# PIC16F15376-breakout.net
KiCad netlist of a schematic drawn in EAGLE
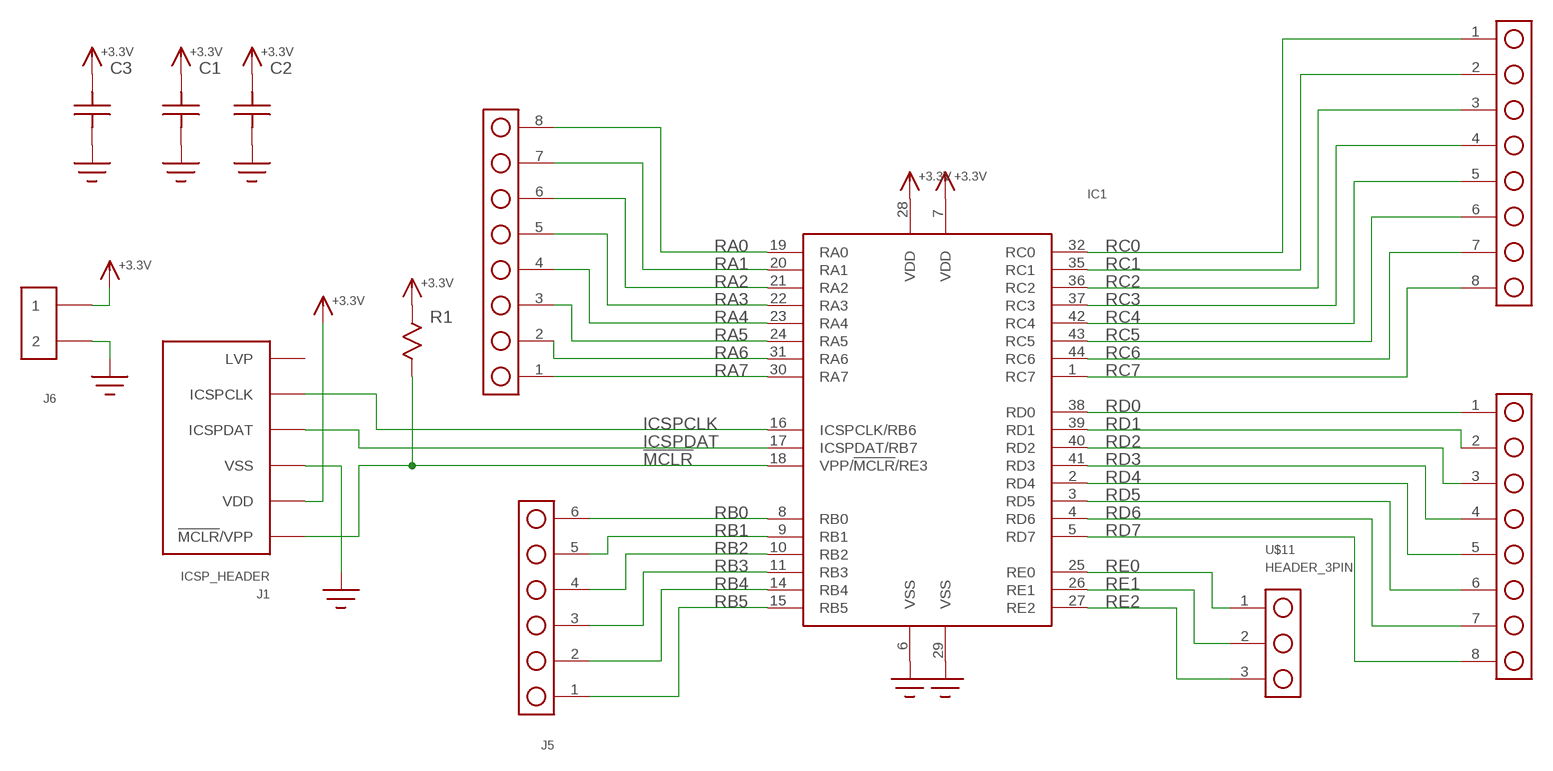
[diagram p0: schematic, sheet 1]

(export (version "E")
  (design (tool "Eeschema 10.0.6"))
  (components
    (comp (ref "C1")
      (value "C0603")
      (footprint "eagle-import:C0603")
      (libsource (lib "eagle-import") (part "C0603"))
    )
    (comp (ref "C2")
      (value "C0603")
      (footprint "eagle-import:C0603")
      (libsource (lib "eagle-import") (part "C0603"))
    )
    (comp (ref "C3")
      (value "C1206")
      (footprint "eagle-import:1206")
      (libsource (lib "eagle-import") (part "C1206"))
    )
    (comp (ref "IC1")
      (value "PIC16F15376")
      (footprint "eagle-import:TQFP44")
      (libsource (lib "eagle-import") (part "PIC16F15376"))
    )
    (comp (ref "J1")
      (value "ICSP_HEADER")
      (footprint "eagle-import:HEADER_6PIN")
      (libsource (lib "eagle-import") (part "ICSP_HEADER"))
    )
    (comp (ref "J2")
      (value "HEADER_8PIN")
      (footprint "eagle-import:HEADER_8_PIN")
      (libsource (lib "eagle-import") (part "HEADER_8PIN"))
    )
    (comp (ref "J3")
      (value "HEADER_8PIN")
      (footprint "eagle-import:HEADER_8_PIN")
      (libsource (lib "eagle-import") (part "HEADER_8PIN"))
    )
    (comp (ref "J4")
      (value "HEADER_8PIN")
      (footprint "eagle-import:HEADER_8_PIN")
      (libsource (lib "eagle-import") (part "HEADER_8PIN"))
    )
    (comp (ref "J5")
      (value "HEADER_6PIN")
      (footprint "eagle-import:HEADER_6PIN")
      (libsource (lib "eagle-import") (part "HEADER_6PIN"))
    )
    (comp (ref "J6")
      (value "HEADER_2PIN")
      (footprint "eagle-import:HEADER_2PIN")
      (libsource (lib "eagle-import") (part "HEADER_2PIN"))
    )
    (comp (ref "R1")
      (value "R0603")
      (footprint "eagle-import:R0603")
      (libsource (lib "eagle-import") (part "R0603"))
    )
    (comp (ref "U$11")
      (value "HEADER_3PIN")
      (footprint "eagle-import:HEADER_3PIN")
      (libsource (lib "eagle-import") (part "HEADER_3PIN"))
    )
  )
  (nets
    (net (code "1") (name "+3.3V") (class "Default")
      (node (ref "C1") (pin "P$2") (pinfunction "P$2_P$2") (pintype "bidirectional"))
      (node (ref "C2") (pin "P$2") (pinfunction "P$2_P$2") (pintype "bidirectional"))
      (node (ref "C3") (pin "P$2") (pinfunction "P$2_P$2") (pintype "bidirectional"))
      (node (ref "IC1") (pin "28") (pinfunction "VDD_28") (pintype "bidirectional"))
      (node (ref "IC1") (pin "7") (pinfunction "VDD_7") (pintype "bidirectional"))
      (node (ref "J1") (pin "2") (pinfunction "VDD_2") (pintype "bidirectional"))
      (node (ref "J6") (pin "1") (pinfunction "1_1") (pintype "bidirectional"))
      (node (ref "R1") (pin "P$1") (pinfunction "P$3_P$1") (pintype "bidirectional"))
    )
    (net (code "2") (name "/ICSPCLK") (class "Default")
      (node (ref "IC1") (pin "16") (pinfunction "ICSPCLK/RB6_16") (pintype "bidirectional"))
      (node (ref "J1") (pin "5") (pinfunction "ICSPCLK_5") (pintype "bidirectional"))
    )
    (net (code "3") (name "/ICSPDAT") (class "Default")
      (node (ref "IC1") (pin "17") (pinfunction "ICSPDAT/RB7_17") (pintype "bidirectional"))
      (node (ref "J1") (pin "4") (pinfunction "ICSPDAT_4") (pintype "bidirectional"))
    )
    (net (code "4") (name "/RA0") (class "Default")
      (node (ref "IC1") (pin "19") (pinfunction "RA0_19") (pintype "bidirectional"))
      (node (ref "J2") (pin "8") (pinfunction "8_8") (pintype "bidirectional"))
    )
    (net (code "5") (name "/RA1") (class "Default")
      (node (ref "IC1") (pin "20") (pinfunction "RA1_20") (pintype "bidirectional"))
      (node (ref "J2") (pin "7") (pinfunction "7_7") (pintype "bidirectional"))
    )
    (net (code "6") (name "/RA2") (class "Default")
      (node (ref "IC1") (pin "21") (pinfunction "RA2_21") (pintype "bidirectional"))
      (node (ref "J2") (pin "6") (pinfunction "6_6") (pintype "bidirectional"))
    )
    (net (code "7") (name "/RA3") (class "Default")
      (node (ref "IC1") (pin "22") (pinfunction "RA3_22") (pintype "bidirectional"))
      (node (ref "J2") (pin "5") (pinfunction "5_5") (pintype "bidirectional"))
    )
    (net (code "8") (name "/RA4") (class "Default")
      (node (ref "IC1") (pin "23") (pinfunction "RA4_23") (pintype "bidirectional"))
      (node (ref "J2") (pin "4") (pinfunction "4_4") (pintype "bidirectional"))
    )
    (net (code "9") (name "/RA5") (class "Default")
      (node (ref "IC1") (pin "24") (pinfunction "RA5_24") (pintype "bidirectional"))
      (node (ref "J2") (pin "3") (pinfunction "3_3") (pintype "bidirectional"))
    )
    (net (code "10") (name "/RA6") (class "Default")
      (node (ref "IC1") (pin "31") (pinfunction "RA6_31") (pintype "bidirectional"))
      (node (ref "J2") (pin "2") (pinfunction "2_2") (pintype "bidirectional"))
    )
    (net (code "11") (name "/RA7") (class "Default")
      (node (ref "IC1") (pin "30") (pinfunction "RA7_30") (pintype "bidirectional"))
      (node (ref "J2") (pin "1") (pinfunction "1_1") (pintype "bidirectional"))
    )
    (net (code "12") (name "/RB0") (class "Default")
      (node (ref "IC1") (pin "8") (pinfunction "RB0_8") (pintype "bidirectional"))
      (node (ref "J5") (pin "6") (pinfunction "6_6") (pintype "bidirectional"))
    )
    (net (code "13") (name "/RB1") (class "Default")
      (node (ref "IC1") (pin "9") (pinfunction "RB1_9") (pintype "bidirectional"))
      (node (ref "J5") (pin "5") (pinfunction "5_5") (pintype "bidirectional"))
    )
    (net (code "14") (name "/RB2") (class "Default")
      (node (ref "IC1") (pin "10") (pinfunction "RB2_10") (pintype "bidirectional"))
      (node (ref "J5") (pin "4") (pinfunction "4_4") (pintype "bidirectional"))
    )
    (net (code "15") (name "/RB3") (class "Default")
      (node (ref "IC1") (pin "11") (pinfunction "RB3_11") (pintype "bidirectional"))
      (node (ref "J5") (pin "3") (pinfunction "3_3") (pintype "bidirectional"))
    )
    (net (code "16") (name "/RB4") (class "Default")
      (node (ref "IC1") (pin "14") (pinfunction "RB4_14") (pintype "bidirectional"))
      (node (ref "J5") (pin "2") (pinfunction "2_2") (pintype "bidirectional"))
    )
    (net (code "17") (name "/RB5") (class "Default")
      (node (ref "IC1") (pin "15") (pinfunction "RB5_15") (pintype "bidirectional"))
      (node (ref "J5") (pin "1") (pinfunction "1_1") (pintype "bidirectional"))
    )
    (net (code "18") (name "/RC0") (class "Default")
      (node (ref "IC1") (pin "32") (pinfunction "RC0_32") (pintype "bidirectional"))
      (node (ref "J3") (pin "1") (pinfunction "1_1") (pintype "bidirectional"))
    )
    (net (code "19") (name "/RC1") (class "Default")
      (node (ref "IC1") (pin "35") (pinfunction "RC1_35") (pintype "bidirectional"))
      (node (ref "J3") (pin "2") (pinfunction "2_2") (pintype "bidirectional"))
    )
    (net (code "20") (name "/RC2") (class "Default")
      (node (ref "IC1") (pin "36") (pinfunction "RC2_36") (pintype "bidirectional"))
      (node (ref "J3") (pin "3") (pinfunction "3_3") (pintype "bidirectional"))
    )
    (net (code "21") (name "/RC3") (class "Default")
      (node (ref "IC1") (pin "37") (pinfunction "RC3_37") (pintype "bidirectional"))
      (node (ref "J3") (pin "4") (pinfunction "4_4") (pintype "bidirectional"))
    )
    (net (code "22") (name "/RC4") (class "Default")
      (node (ref "IC1") (pin "42") (pinfunction "RC4_42") (pintype "bidirectional"))
      (node (ref "J3") (pin "5") (pinfunction "5_5") (pintype "bidirectional"))
    )
    (net (code "23") (name "/RC5") (class "Default")
      (node (ref "IC1") (pin "43") (pinfunction "RC5_43") (pintype "bidirectional"))
      (node (ref "J3") (pin "6") (pinfunction "6_6") (pintype "bidirectional"))
    )
    (net (code "24") (name "/RC6") (class "Default")
      (node (ref "IC1") (pin "44") (pinfunction "RC6_44") (pintype "bidirectional"))
      (node (ref "J3") (pin "7") (pinfunction "7_7") (pintype "bidirectional"))
    )
    (net (code "25") (name "/RC7") (class "Default")
      (node (ref "IC1") (pin "1") (pinfunction "RC7_1") (pintype "bidirectional"))
      (node (ref "J3") (pin "8") (pinfunction "8_8") (pintype "bidirectional"))
    )
    (net (code "26") (name "/RD0") (class "Default")
      (node (ref "IC1") (pin "38") (pinfunction "RD0_38") (pintype "bidirectional"))
      (node (ref "J4") (pin "1") (pinfunction "1_1") (pintype "bidirectional"))
    )
    (net (code "27") (name "/RD1") (class "Default")
      (node (ref "IC1") (pin "39") (pinfunction "RD1_39") (pintype "bidirectional"))
      (node (ref "J4") (pin "2") (pinfunction "2_2") (pintype "bidirectional"))
    )
    (net (code "28") (name "/RD2") (class "Default")
      (node (ref "IC1") (pin "40") (pinfunction "RD2_40") (pintype "bidirectional"))
      (node (ref "J4") (pin "3") (pinfunction "3_3") (pintype "bidirectional"))
    )
    (net (code "29") (name "/RD3") (class "Default")
      (node (ref "IC1") (pin "41") (pinfunction "RD3_41") (pintype "bidirectional"))
      (node (ref "J4") (pin "4") (pinfunction "4_4") (pintype "bidirectional"))
    )
    (net (code "30") (name "/RD4") (class "Default")
      (node (ref "IC1") (pin "2") (pinfunction "RD4_2") (pintype "bidirectional"))
      (node (ref "J4") (pin "5") (pinfunction "5_5") (pintype "bidirectional"))
    )
    (net (code "31") (name "/RD5") (class "Default")
      (node (ref "IC1") (pin "3") (pinfunction "RD5_3") (pintype "bidirectional"))
      (node (ref "J4") (pin "6") (pinfunction "6_6") (pintype "bidirectional"))
    )
    (net (code "32") (name "/RD6") (class "Default")
      (node (ref "IC1") (pin "4") (pinfunction "RD6_4") (pintype "bidirectional"))
      (node (ref "J4") (pin "7") (pinfunction "7_7") (pintype "bidirectional"))
    )
    (net (code "33") (name "/RD7") (class "Default")
      (node (ref "IC1") (pin "5") (pinfunction "RD7_5") (pintype "bidirectional"))
      (node (ref "J4") (pin "8") (pinfunction "8_8") (pintype "bidirectional"))
    )
    (net (code "34") (name "/RE0") (class "Default")
      (node (ref "IC1") (pin "25") (pinfunction "RE0_25") (pintype "bidirectional"))
      (node (ref "U$11") (pin "1") (pinfunction "1_1") (pintype "bidirectional"))
    )
    (net (code "35") (name "/RE1") (class "Default")
      (node (ref "IC1") (pin "26") (pinfunction "RE1_26") (pintype "bidirectional"))
      (node (ref "U$11") (pin "2") (pinfunction "2_2") (pintype "bidirectional"))
    )
    (net (code "36") (name "/RE2") (class "Default")
      (node (ref "IC1") (pin "27") (pinfunction "RE2_27") (pintype "bidirectional"))
      (node (ref "U$11") (pin "3") (pinfunction "3_3") (pintype "bidirectional"))
    )
    (net (code "37") (name "/~{MCLR}") (class "Default")
      (node (ref "IC1") (pin "18") (pinfunction "VPP/~{MCLR}/RE3_18") (pintype "bidirectional"))
      (node (ref "J1") (pin "1") (pinfunction "~{MCLR}/VPP_1") (pintype "bidirectional"))
      (node (ref "R1") (pin "P$2") (pinfunction "P$4_P$2") (pintype "bidirectional"))
    )
    (net (code "38") (name "GND") (class "Default")
      (node (ref "C1") (pin "P$1") (pinfunction "P$1_P$1") (pintype "bidirectional"))
      (node (ref "C2") (pin "P$1") (pinfunction "P$1_P$1") (pintype "bidirectional"))
      (node (ref "C3") (pin "P$1") (pinfunction "P$1_P$1") (pintype "bidirectional"))
      (node (ref "IC1") (pin "29") (pinfunction "VSS_29") (pintype "bidirectional"))
      (node (ref "IC1") (pin "6") (pinfunction "VSS_6") (pintype "bidirectional"))
      (node (ref "J1") (pin "3") (pinfunction "VSS_3") (pintype "bidirectional"))
      (node (ref "J6") (pin "2") (pinfunction "2_2") (pintype "bidirectional"))
    )
    (net (code "39") (name "unconnected-(J1-LVP-Pad6)") (class "Default")
      (node (ref "J1") (pin "6") (pinfunction "LVP_6") (pintype "bidirectional"))
    )
  )
)
